# Peripherals_-_Feature_Creep.net
KiCad netlist of a schematic drawn in Altium Designer
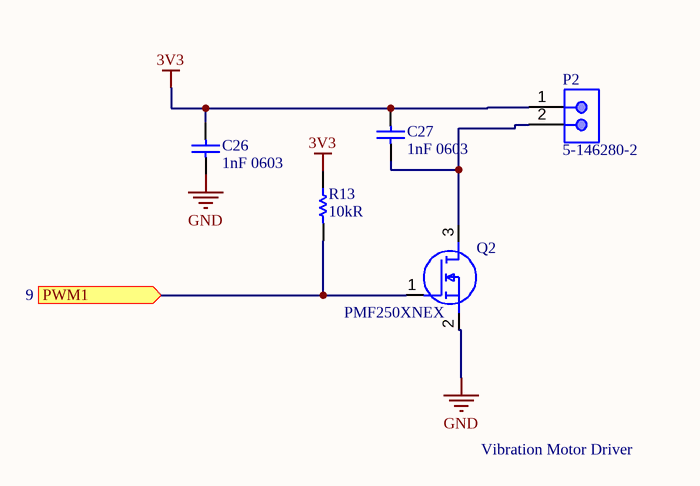
[diagram p0: Peripherals - Feature Creep.SchDoc]

(export (version "E")
  (design (tool "Eeschema 10.0.6"))
  (components
    (comp (ref "C26")
      (value "1nF 0603")
      (footprint "CAPC1608X90X35LL15T15")
      (description "06035C102KAT2A")
      (fields (field (name "MANUFACTURER") "AVX Interconnect / Elco"))
      (libsource (lib "Altium Content Vault") (part "CAP"))
    )
    (comp (ref "C27")
      (value "1nF 0603")
      (footprint "CAPC1608X90X35LL15T15")
      (description "06035C102KAT2A")
      (fields (field (name "MANUFACTURER") "AVX Interconnect / Elco"))
      (libsource (lib "Altium Content Vault") (part "CAP"))
    )
    (comp (ref "P2")
      (value "5-146280-2")
      (footprint "TECO-5-146280-2_V")
      (fields (field (name "MANUFACTURER") "TE Connectivity"))
      (libsource (lib "Altium Content Vault") (part "CN-1P-M-R2"))
    )
    (comp (ref "Q2")
      (value "PMF250XNEX")
      (footprint "LayoutFootprintsGoogle:SOT65P210X110-3N")
      (description "MOSFET (N-Channel)")
      (fields (field (name "MOUSER PART NUMBER") "771-PMF250XNEX"))
      (libsource (lib "*") (part "PMF250XNEX"))
    )
    (comp (ref "R13")
      (value "10kR")
      (footprint "RESC2013X60X35NL10T20")
      (fields (field (name "MANUFACTURER") "Yageo"))
      (libsource (lib "Altium Content Vault") (part "RES-2"))
    )
  )
  (nets
    (net (code "1") (name "/PWM1") (class "Default")
      (node (ref "Q2") (pin "1") (pinfunction "G_1") (pintype "passive"))
      (node (ref "R13") (pin "2") (pinfunction "2_2") (pintype "passive"))
    )
    (net (code "2") (name "3V3") (class "Default")
      (node (ref "C26") (pin "1") (pinfunction "1_1") (pintype "passive"))
      (node (ref "C27") (pin "1") (pinfunction "1_1") (pintype "passive"))
      (node (ref "P2") (pin "1") (pinfunction "1_1") (pintype "passive"))
      (node (ref "R13") (pin "1") (pinfunction "1_1") (pintype "passive"))
    )
    (net (code "3") (name "GND") (class "Default")
      (node (ref "C26") (pin "2") (pinfunction "2_2") (pintype "passive"))
      (node (ref "Q2") (pin "2") (pinfunction "S_2") (pintype "passive"))
    )
    (net (code "4") (name "Net-(Q2-D)") (class "Default")
      (node (ref "C27") (pin "2") (pinfunction "2_2") (pintype "passive"))
      (node (ref "P2") (pin "2") (pinfunction "2_2") (pintype "passive"))
      (node (ref "Q2") (pin "3") (pinfunction "D_3") (pintype "passive"))
    )
  )
)
